# USB-UART_PL2303_HX.net
KiCad netlist of a schematic drawn in Altium Designer
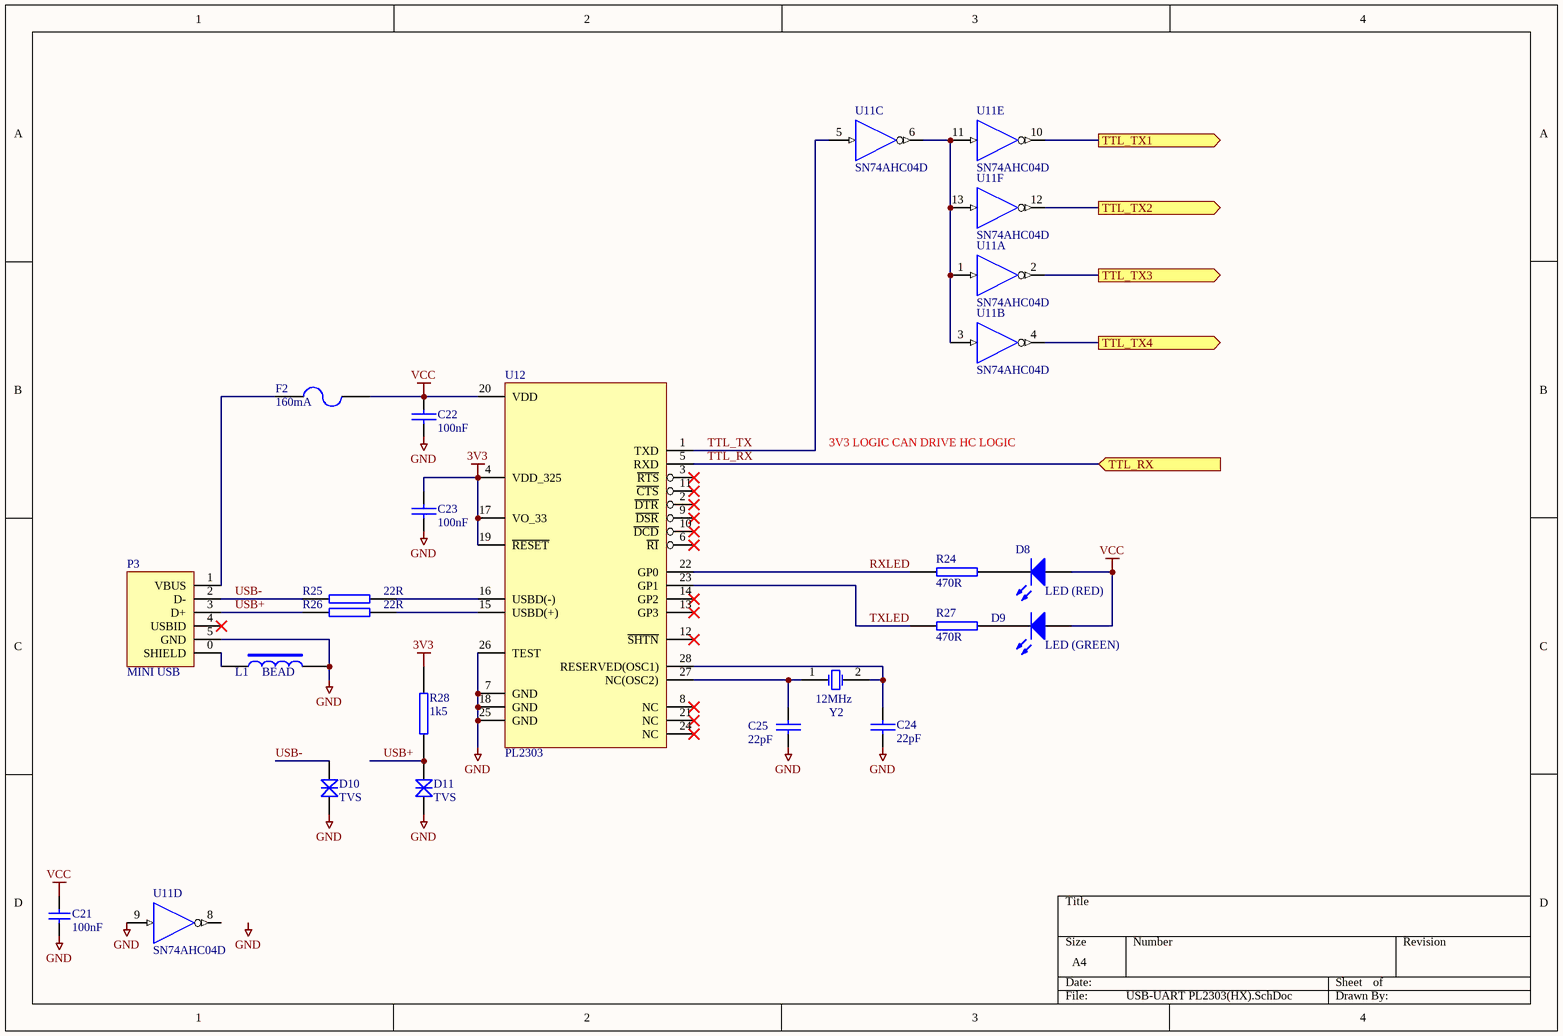
[diagram p0: USB-UART PL2303(HX).SchDoc]

(export (version "E")
  (design (tool "Eeschema 10.0.6"))
  (components
    (comp (ref "C21")
      (value "100nF")
      (footprint "CAP (3D) - 0603")
      (description "Capacitor")
      (libsource (lib "Miscellaneous Devices") (part "Cap"))
    )
    (comp (ref "C22")
      (value "100nF")
      (footprint "CAP (3D) - 0603")
      (description "CAPACITOR SMD 0603")
      (fields (field (name "MOUSER PART NO.") "81-GCM188R71C104KA7D") (field (name "MANUFACTURER") "Murata"))
      (libsource (lib "NASCO Capacitors") (part "CAP SMD 0603 100nF"))
    )
    (comp (ref "C23")
      (value "100nF")
      (footprint "CAP (3D) - 0603")
      (description "CAPACITOR SMD 0603")
      (fields (field (name "MOUSER PART NO.") "81-GCM188R71C104KA7D") (field (name "MANUFACTURER") "Murata"))
      (libsource (lib "NASCO Capacitors") (part "CAP SMD 0603 100nF"))
    )
    (comp (ref "C24")
      (value "22pF")
      (footprint "CAP (3D) - 0603")
      (description "CAPACITOR SMD 0603")
      (fields
        (field (name "MANUFACTURER") "Vishay")
        (field (name "MANUFACTURER PART NO.") "VJ0603A220JXACW1BC")
      )
      (libsource (lib "NASCO Capacitors") (part "CAP SMD 0603 1nF"))
    )
    (comp (ref "C25")
      (value "22pF")
      (footprint "CAP (3D) - 0603")
      (description "CAPACITOR SMD 0603")
      (fields
        (field (name "MANUFACTURER") "Vishay")
        (field (name "MANUFACTURER PART NO.") "VJ0603A220JXACW1BC")
      )
      (libsource (lib "NASCO Capacitors") (part "CAP SMD 0603 1nF"))
    )
    (comp (ref "D8")
      (value "LED (RED)")
      (footprint "LED(3D) 3MM VERTICAL (RED)")
      (description "3mm RED LED")
      (fields (field (name "MOUSER PART NO.") "859-LTL-4261NR") (field (name "MANUFACTURER") "Lite-On"))
      (libsource (lib "NASCO") (part "LED 3mm RED"))
    )
    (comp (ref "D9")
      (value "LED (GREEN)")
      (footprint "LED(3D) 3MM VERTICAL (GREEN)")
      (description "3mm GREEN LED")
      (fields (field (name "MOUSER PART NO.") "859-LTL-1CHG") (field (name "MANUFACTURER") "Lite-On"))
      (libsource (lib "NASCO") (part "LED 3mm GREEN"))
    )
    (comp (ref "D10")
      (value "TVS")
      (footprint "TVS (3D) - 0603")
      (description "Transient Voltage Suppression (TVS) Diode")
      (fields (field (name "MANUFACTURER PART NO.") "CG0603MLC-05E") (field (name "MANUFACTURER") "Bourns"))
      (libsource (lib "SIM900") (part "TVS DIODE"))
    )
    (comp (ref "D11")
      (value "TVS")
      (footprint "TVS (3D) - 0603")
      (description "Transient Voltage Suppression (TVS) Diode")
      (fields (field (name "MANUFACTURER PART NO.") "CG0603MLC-05E") (field (name "MANUFACTURER") "Bourns"))
      (libsource (lib "SIM900") (part "TVS DIODE"))
    )
    (comp (ref "F2")
      (value "160mA")
      (footprint "1206")
      (description "Fuse")
      (fields (field (name "MANUFACTURER") "Littlefuse") (field (name "MOUSER PART NO.") "576-1206L016WR"))
      (libsource (lib "Miscellaneous Devices") (part "Fuse 2"))
    )
    (comp (ref "L1")
      (value "BEAD")
      (footprint "RES (3D) - 1210")
      (description "INDUCTOR SMD 1210")
      (fields (field (name "MOUSER PART NO.") "636-2512063007Y3") (field (name "MANUFACTURER") "Fair-Rite"))
      (libsource (lib "NASCO") (part "INDUCTOR SMD 1210 100uH"))
    )
    (comp (ref "P3")
      (value "MINI USB")
      (footprint "MINI USB")
      (description "MICRO USB")
      (fields
        (field (name "MANUFACTURER") "Keystone Electronics")
        (field (name "MANUFACTURER PART NO.") "534-934")
      )
      (libsource (lib "SIM900") (part "MICRO USB"))
    )
    (comp (ref "R24")
      (value "470R")
      (footprint "RES (3D) - 0603")
      (description "RESISTOR SMD 0603 590R")
      (fields (field (name "MOUSER PART NO.") "71-CRCW0603J-470-E3") (field (name "MANUFACTURER") "Vishay"))
      (libsource (lib "NASCO Resistors") (part "RES SMD 0603 590R"))
    )
    (comp (ref "R25")
      (value "22R")
      (footprint "RES (3D) - 0603")
      (description "RESISTOR SMD 0603 0R")
      (fields (field (name "MANUFACTURER") "Xicon") (field (name "MANUFACTURER PART NO.") "301-22-RC"))
      (libsource (lib "NASCO Resistors") (part "RES SMD 0603 0R"))
    )
    (comp (ref "R26")
      (value "22R")
      (footprint "RES (3D) - 0603")
      (description "RESISTOR SMD 0603 0R")
      (fields (field (name "MANUFACTURER") "Xicon") (field (name "MANUFACTURER PART NO.") "301-22-RC"))
      (libsource (lib "NASCO Resistors") (part "RES SMD 0603 0R"))
    )
    (comp (ref "R27")
      (value "470R")
      (footprint "RES (3D) - 0603")
      (description "RESISTOR SMD 0603 590R")
      (fields (field (name "MOUSER PART NO.") "71-CRCW0603J-470-E3") (field (name "MANUFACTURER") "Vishay"))
      (libsource (lib "NASCO Resistors") (part "RES SMD 0603 590R"))
    )
    (comp (ref "R28")
      (value "1k5")
      (footprint "RES (3D) - 0603")
      (description "RESISTOR SMD 0603 0R")
      (libsource (lib "NASCO Resistors") (part "RES SMD 0603 0R"))
    )
    (comp (ref "U11")
      (value "SN74AHC04D")
      (footprint "SOIC-14")
      (description "Hex Inverter")
      (fields (field (name "PUBLISHER") "Altium Limited"))
      (libsource (lib "TI Logic Gate 1") (part "SN74AHC04D"))
    )
    (comp (ref "U12")
      (value "PL2303")
      (footprint "SSOP28")
      (description "PL2303 USB to 232 Converter (FT232 Compatible)")
      (libsource (lib "NASCO") (part "PL2303"))
    )
    (comp (ref "Y2")
      (value "12MHz")
      (footprint "CRYSTAL 3x8")
      (description "Crystal Oscillator")
      (fields (field (name "Comment") "XTAL"))
      (libsource (lib "Miscellaneous Devices") (part "XTAL"))
    )
  )
  (nets
    (net (code "1") (name "/RXLED") (class "Default")
      (node (ref "R24") (pin "1") (pinfunction "1_1") (pintype "passive"))
      (node (ref "U12") (pin "22") (pinfunction "GP0_22") (pintype "passive"))
    )
    (net (code "2") (name "/TTL_RX") (class "Default")
      (node (ref "U12") (pin "5") (pinfunction "RXD_5") (pintype "passive"))
    )
    (net (code "3") (name "/TTL_TX") (class "Default")
      (node (ref "U11") (pin "5") (pinfunction "A_5") (pintype "input"))
      (node (ref "U12") (pin "1") (pinfunction "TXD_1") (pintype "passive"))
    )
    (net (code "4") (name "/TTL_TX1") (class "Default")
      (node (ref "U11") (pin "10") (pinfunction "Y_10") (pintype "output"))
    )
    (net (code "5") (name "/TTL_TX2") (class "Default")
      (node (ref "U11") (pin "12") (pinfunction "Y_12") (pintype "output"))
    )
    (net (code "6") (name "/TTL_TX3") (class "Default")
      (node (ref "U11") (pin "2") (pinfunction "Y_2") (pintype "output"))
    )
    (net (code "7") (name "/TTL_TX4") (class "Default")
      (node (ref "U11") (pin "4") (pinfunction "Y_4") (pintype "output"))
    )
    (net (code "8") (name "/TXLED") (class "Default")
      (node (ref "R27") (pin "1") (pinfunction "1_1") (pintype "passive"))
      (node (ref "U12") (pin "23") (pinfunction "GP1_23") (pintype "passive"))
    )
    (net (code "9") (name "/USB+") (class "Default")
      (node (ref "D11") (pin "2") (pinfunction "K_2") (pintype "passive"))
      (node (ref "P3") (pin "3") (pinfunction "D+_3") (pintype "passive"))
      (node (ref "R26") (pin "1") (pinfunction "1_1") (pintype "passive"))
      (node (ref "R28") (pin "2") (pinfunction "2_2") (pintype "passive"))
    )
    (net (code "10") (name "/USB-") (class "Default")
      (node (ref "D10") (pin "2") (pinfunction "K_2") (pintype "passive"))
      (node (ref "P3") (pin "2") (pinfunction "D-_2") (pintype "passive"))
      (node (ref "R25") (pin "1") (pinfunction "1_1") (pintype "passive"))
    )
    (net (code "11") (name "3V3") (class "Default")
      (node (ref "C23") (pin "1") (pinfunction "1_1") (pintype "passive"))
      (node (ref "R28") (pin "1") (pinfunction "1_1") (pintype "passive"))
      (node (ref "U12") (pin "17") (pinfunction "VO_33_17") (pintype "passive"))
      (node (ref "U12") (pin "19") (pinfunction "~{RESET}_19") (pintype "passive"))
      (node (ref "U12") (pin "4") (pinfunction "VDD_325_4") (pintype "passive"))
    )
    (net (code "12") (name "GND") (class "Default")
      (node (ref "C21") (pin "1") (pinfunction "1_1") (pintype "passive"))
      (node (ref "C22") (pin "2") (pinfunction "2_2") (pintype "passive"))
      (node (ref "C23") (pin "2") (pinfunction "2_2") (pintype "passive"))
      (node (ref "C24") (pin "2") (pinfunction "2_2") (pintype "passive"))
      (node (ref "C25") (pin "2") (pinfunction "2_2") (pintype "passive"))
      (node (ref "D10") (pin "1") (pinfunction "A_1") (pintype "passive"))
      (node (ref "D11") (pin "1") (pinfunction "A_1") (pintype "passive"))
      (node (ref "L1") (pin "2") (pinfunction "2_2") (pintype "passive"))
      (node (ref "P3") (pin "5") (pinfunction "GND_5") (pintype "passive"))
      (node (ref "U11") (pin "7") (pinfunction "GND_7") (pintype "power_in"))
      (node (ref "U11") (pin "9") (pinfunction "A_9") (pintype "input"))
      (node (ref "U12") (pin "18") (pinfunction "GND_18") (pintype "passive"))
      (node (ref "U12") (pin "25") (pinfunction "GND_25") (pintype "passive"))
      (node (ref "U12") (pin "26") (pinfunction "TEST_26") (pintype "passive"))
      (node (ref "U12") (pin "7") (pinfunction "GND_7") (pintype "passive"))
    )
    (net (code "13") (name "Net-(D8-K)") (class "Default")
      (node (ref "D8") (pin "2") (pinfunction "K_2") (pintype "passive"))
      (node (ref "R24") (pin "2") (pinfunction "2_2") (pintype "passive"))
    )
    (net (code "14") (name "Net-(D9-K)") (class "Default")
      (node (ref "D9") (pin "2") (pinfunction "K_2") (pintype "passive"))
      (node (ref "R27") (pin "2") (pinfunction "2_2") (pintype "passive"))
    )
    (net (code "15") (name "Net-(P3-SHIELD)") (class "Default")
      (node (ref "L1") (pin "1") (pinfunction "1_1") (pintype "passive"))
      (node (ref "P3") (pin "0") (pinfunction "SHIELD_0") (pintype "passive"))
    )
    (net (code "16") (name "Net-(P3-VBUS)") (class "Default")
      (node (ref "F2") (pin "1") (pinfunction "1_1") (pintype "passive"))
      (node (ref "P3") (pin "1") (pinfunction "VBUS_1") (pintype "passive"))
    )
    (net (code "17") (name "Net-(U11A-A)") (class "Default")
      (node (ref "U11") (pin "1") (pinfunction "A_1") (pintype "input"))
      (node (ref "U11") (pin "11") (pinfunction "A_11") (pintype "input"))
      (node (ref "U11") (pin "13") (pinfunction "A_13") (pintype "input"))
      (node (ref "U11") (pin "3") (pinfunction "A_3") (pintype "input"))
      (node (ref "U11") (pin "6") (pinfunction "Y_6") (pintype "output"))
    )
    (net (code "18") (name "Net-(U12-NC(OSC2))") (class "Default")
      (node (ref "C25") (pin "1") (pinfunction "1_1") (pintype "passive"))
      (node (ref "U12") (pin "27") (pinfunction "NC(OSC2)_27") (pintype "passive"))
      (node (ref "Y2") (pin "1") (pinfunction "OSC1_1") (pintype "passive"))
    )
    (net (code "19") (name "Net-(U12-RESERVED(OSC1))") (class "Default")
      (node (ref "C24") (pin "1") (pinfunction "1_1") (pintype "passive"))
      (node (ref "U12") (pin "28") (pinfunction "RESERVED(OSC1)_28") (pintype "passive"))
      (node (ref "Y2") (pin "2") (pinfunction "OSC2_2") (pintype "passive"))
    )
    (net (code "20") (name "Net-(U12-USBD(+))") (class "Default")
      (node (ref "R26") (pin "2") (pinfunction "2_2") (pintype "passive"))
      (node (ref "U12") (pin "15") (pinfunction "USBD(+)_15") (pintype "passive"))
    )
    (net (code "21") (name "Net-(U12-USBD(-))") (class "Default")
      (node (ref "R25") (pin "2") (pinfunction "2_2") (pintype "passive"))
      (node (ref "U12") (pin "16") (pinfunction "USBD(-)_16") (pintype "passive"))
    )
    (net (code "22") (name "VCC") (class "Default")
      (node (ref "C21") (pin "2") (pinfunction "2_2") (pintype "passive"))
      (node (ref "C22") (pin "1") (pinfunction "1_1") (pintype "passive"))
      (node (ref "D8") (pin "1") (pinfunction "A_1") (pintype "passive"))
      (node (ref "D9") (pin "1") (pinfunction "A_1") (pintype "passive"))
      (node (ref "F2") (pin "2") (pinfunction "2_2") (pintype "passive"))
      (node (ref "U11") (pin "14") (pinfunction "VCC_14") (pintype "power_in"))
      (node (ref "U12") (pin "20") (pinfunction "VDD_20") (pintype "passive"))
    )
    (net (code "23") (name "unconnected-(P3-USBID-Pad4)") (class "Default")
      (node (ref "P3") (pin "4") (pinfunction "USBID_4") (pintype "passive+no_connect"))
    )
    (net (code "24") (name "unconnected-(U11D-Y-Pad8)") (class "Default")
      (node (ref "U11") (pin "8") (pinfunction "Y_8") (pintype "output"))
    )
    (net (code "25") (name "unconnected-(U12-GP2-Pad14)") (class "Default")
      (node (ref "U12") (pin "14") (pinfunction "GP2_14") (pintype "passive+no_connect"))
    )
    (net (code "26") (name "unconnected-(U12-GP3-Pad13)") (class "Default")
      (node (ref "U12") (pin "13") (pinfunction "GP3_13") (pintype "passive+no_connect"))
    )
    (net (code "27") (name "unconnected-(U12-NC-Pad8)") (class "Default")
      (node (ref "U12") (pin "8") (pinfunction "NC_8") (pintype "passive+no_connect"))
    )
    (net (code "28") (name "unconnected-(U12-NC-Pad21)") (class "Default")
      (node (ref "U12") (pin "21") (pinfunction "NC_21") (pintype "passive+no_connect"))
    )
    (net (code "29") (name "unconnected-(U12-NC-Pad24)") (class "Default")
      (node (ref "U12") (pin "24") (pinfunction "NC_24") (pintype "passive+no_connect"))
    )
    (net (code "30") (name "unconnected-(U12-~{CTS}-Pad11)") (class "Default")
      (node (ref "U12") (pin "11") (pinfunction "~{CTS}_11") (pintype "passive+no_connect"))
    )
    (net (code "31") (name "unconnected-(U12-~{DCD}-Pad10)") (class "Default")
      (node (ref "U12") (pin "10") (pinfunction "~{DCD}_10") (pintype "passive+no_connect"))
    )
    (net (code "32") (name "unconnected-(U12-~{DSR}-Pad9)") (class "Default")
      (node (ref "U12") (pin "9") (pinfunction "~{DSR}_9") (pintype "passive+no_connect"))
    )
    (net (code "33") (name "unconnected-(U12-~{DTR}-Pad2)") (class "Default")
      (node (ref "U12") (pin "2") (pinfunction "~{DTR}_2") (pintype "passive+no_connect"))
    )
    (net (code "34") (name "unconnected-(U12-~{RI}-Pad6)") (class "Default")
      (node (ref "U12") (pin "6") (pinfunction "~{RI}_6") (pintype "passive+no_connect"))
    )
    (net (code "35") (name "unconnected-(U12-~{RTS}-Pad3)") (class "Default")
      (node (ref "U12") (pin "3") (pinfunction "~{RTS}_3") (pintype "passive+no_connect"))
    )
    (net (code "36") (name "unconnected-(U12-~{SHTN}-Pad12)") (class "Default")
      (node (ref "U12") (pin "12") (pinfunction "~{SHTN}_12") (pintype "passive+no_connect"))
    )
  )
)
